# 4_PT100.net
KiCad netlist of a schematic drawn in Altium Designer
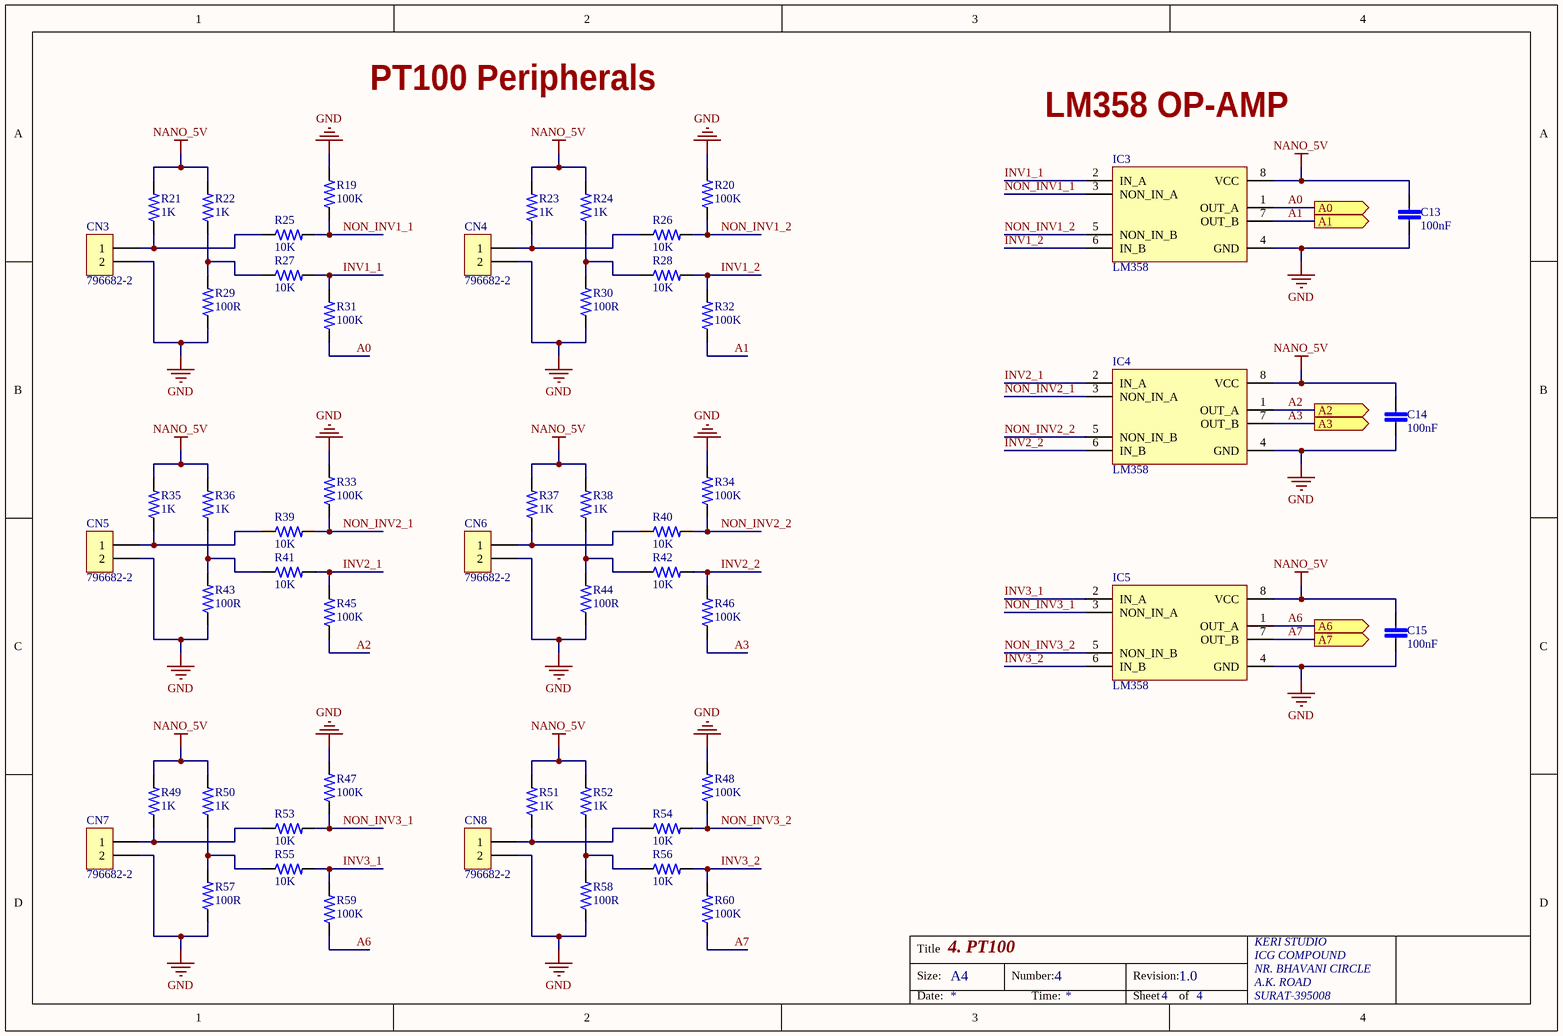
[diagram p0: 4. PT100.SchDoc]

(export (version "E")
  (design (tool "Eeschema 10.0.6"))
  (components
    (comp (ref "C13")
      (value "100nF")
      (footprint "C0805")
      (description "Multilayer Ceramic Capacitors MLCC - SMD/SMT 0805 0.1uF 50volts X7R 20%")
      (fields
        (field (name "MANUFACTURER") "Murata")
        (field (name "MANUFACTURER PART NUMBER") "GCJ21BR71H104MA01L")
      )
      (libsource (lib "keri_lib") (part "C_0805_0.1uF"))
    )
    (comp (ref "C14")
      (value "100nF")
      (footprint "C0805")
      (description "Multilayer Ceramic Capacitors MLCC - SMD/SMT 0805 0.1uF 50volts X7R 20%")
      (fields
        (field (name "MANUFACTURER") "Murata")
        (field (name "MANUFACTURER PART NUMBER") "GCJ21BR71H104MA01L")
      )
      (libsource (lib "keri_lib") (part "C_0805_0.1uF"))
    )
    (comp (ref "C15")
      (value "100nF")
      (footprint "C0805")
      (description "Multilayer Ceramic Capacitors MLCC - SMD/SMT 0805 0.1uF 50volts X7R 20%")
      (fields
        (field (name "MANUFACTURER") "Murata")
        (field (name "MANUFACTURER PART NUMBER") "GCJ21BR71H104MA01L")
      )
      (libsource (lib "keri_lib") (part "C_0805_0.1uF"))
    )
    (comp (ref "CN3")
      (value "796682-2")
      (footprint "Terminal_5.08mm_1X02")
      (description "Fixed Terminal Blocks TERMI-BLOK PCB")
      (fields (field (name "MANUFACTURER") "TE Connectivity") (field (name "VOLTAGE") "300V"))
      (libsource (lib "keri_lib") (part "Terminal_5.08mm_1X02"))
    )
    (comp (ref "CN4")
      (value "796682-2")
      (footprint "Terminal_5.08mm_1X02")
      (description "Fixed Terminal Blocks TERMI-BLOK PCB")
      (fields (field (name "MANUFACTURER") "TE Connectivity") (field (name "VOLTAGE") "300V"))
      (libsource (lib "keri_lib") (part "Terminal_5.08mm_1X02"))
    )
    (comp (ref "CN5")
      (value "796682-2")
      (footprint "Terminal_5.08mm_1X02")
      (description "Fixed Terminal Blocks TERMI-BLOK PCB")
      (fields (field (name "MANUFACTURER") "TE Connectivity") (field (name "VOLTAGE") "300V"))
      (libsource (lib "keri_lib") (part "Terminal_5.08mm_1X02"))
    )
    (comp (ref "CN6")
      (value "796682-2")
      (footprint "Terminal_5.08mm_1X02")
      (description "Fixed Terminal Blocks TERMI-BLOK PCB")
      (fields (field (name "MANUFACTURER") "TE Connectivity") (field (name "VOLTAGE") "300V"))
      (libsource (lib "keri_lib") (part "Terminal_5.08mm_1X02"))
    )
    (comp (ref "CN7")
      (value "796682-2")
      (footprint "Terminal_5.08mm_1X02")
      (description "Fixed Terminal Blocks TERMI-BLOK PCB")
      (fields (field (name "MANUFACTURER") "TE Connectivity") (field (name "VOLTAGE") "300V"))
      (libsource (lib "keri_lib") (part "Terminal_5.08mm_1X02"))
    )
    (comp (ref "CN8")
      (value "796682-2")
      (footprint "Terminal_5.08mm_1X02")
      (description "Fixed Terminal Blocks TERMI-BLOK PCB")
      (fields (field (name "MANUFACTURER") "TE Connectivity") (field (name "VOLTAGE") "300V"))
      (libsource (lib "keri_lib") (part "Terminal_5.08mm_1X02"))
    )
    (comp (ref "IC3")
      (value "LM358")
      (footprint "DIP-08")
      (description "IC OPAMP GP 700KHZ 8SOIC")
      (fields
        (field (name "MANUFACTURER") "Texas Instruments")
        (field (name "MANUFACTURER PART NUMBER") "LM358ADR")
      )
      (libsource (lib "keri_lib") (part "LM358"))
    )
    (comp (ref "IC4")
      (value "LM358")
      (footprint "DIP-08")
      (description "IC OPAMP GP 700KHZ 8SOIC")
      (fields
        (field (name "MANUFACTURER") "Texas Instruments")
        (field (name "MANUFACTURER PART NUMBER") "LM358ADR")
      )
      (libsource (lib "keri_lib") (part "LM358"))
    )
    (comp (ref "IC5")
      (value "LM358")
      (footprint "DIP-08")
      (description "IC OPAMP GP 700KHZ 8SOIC")
      (fields
        (field (name "MANUFACTURER") "Texas Instruments")
        (field (name "MANUFACTURER PART NUMBER") "LM358ADR")
      )
      (libsource (lib "keri_lib") (part "LM358"))
    )
    (comp (ref "R19")
      (value "100K")
      (footprint "R0805")
      (description "Thick Film Resistors - SMD 100K 0805 5%")
      (fields (field (name "MANUFACTURER") "Bourns") (field (name "TOLERANCE") "5%"))
      (libsource (lib "keri_lib") (part "R_0805_100K"))
    )
    (comp (ref "R20")
      (value "100K")
      (footprint "R0805")
      (description "Thick Film Resistors - SMD 100K 0805 5%")
      (fields (field (name "MANUFACTURER") "Bourns") (field (name "TOLERANCE") "5%"))
      (libsource (lib "keri_lib") (part "R_0805_100K"))
    )
    (comp (ref "R21")
      (value "1K")
      (footprint "R0805")
      (description "Thick Film Resistors - SMD 1K 5%")
      (fields
        (field (name "MANUFACTURER") "Bourns")
        (field (name "MANUFACTURER PART NUMBER") "CR0805-JW-102ELF")
      )
      (libsource (lib "keri_lib") (part "R_0805_1K"))
    )
    (comp (ref "R22")
      (value "1K")
      (footprint "R0805")
      (description "Thick Film Resistors - SMD 1K 5%")
      (fields
        (field (name "MANUFACTURER") "Bourns")
        (field (name "MANUFACTURER PART NUMBER") "CR0805-JW-102ELF")
      )
      (libsource (lib "keri_lib") (part "R_0805_1K"))
    )
    (comp (ref "R23")
      (value "1K")
      (footprint "R0805")
      (description "Thick Film Resistors - SMD 1K 5%")
      (fields
        (field (name "MANUFACTURER") "Bourns")
        (field (name "MANUFACTURER PART NUMBER") "CR0805-JW-102ELF")
      )
      (libsource (lib "keri_lib") (part "R_0805_1K"))
    )
    (comp (ref "R24")
      (value "1K")
      (footprint "R0805")
      (description "Thick Film Resistors - SMD 1K 5%")
      (fields
        (field (name "MANUFACTURER") "Bourns")
        (field (name "MANUFACTURER PART NUMBER") "CR0805-JW-102ELF")
      )
      (libsource (lib "keri_lib") (part "R_0805_1K"))
    )
    (comp (ref "R25")
      (value "10K")
      (footprint "R0805")
      (description "Thick Film Resistors - SMD 10K 0805 5%")
      (fields (field (name "MANUFACTURER") "Bourns") (field (name "TOLERANCE") "5%"))
      (libsource (lib "keri_lib") (part "R_0805_10K"))
    )
    (comp (ref "R26")
      (value "10K")
      (footprint "R0805")
      (description "Thick Film Resistors - SMD 10K 0805 5%")
      (fields (field (name "MANUFACTURER") "Bourns") (field (name "TOLERANCE") "5%"))
      (libsource (lib "keri_lib") (part "R_0805_10K"))
    )
    (comp (ref "R27")
      (value "10K")
      (footprint "R0805")
      (description "Thick Film Resistors - SMD 10K 0805 5%")
      (fields (field (name "MANUFACTURER") "Bourns") (field (name "TOLERANCE") "5%"))
      (libsource (lib "keri_lib") (part "R_0805_10K"))
    )
    (comp (ref "R28")
      (value "10K")
      (footprint "R0805")
      (description "Thick Film Resistors - SMD 10K 0805 5%")
      (fields (field (name "MANUFACTURER") "Bourns") (field (name "TOLERANCE") "5%"))
      (libsource (lib "keri_lib") (part "R_0805_10K"))
    )
    (comp (ref "R29")
      (value "100R")
      (footprint "R0805")
      (description "Thick Film Resistors - SMD 10ohm 5%")
      (fields
        (field (name "MANUFACTURER") "Bourns")
        (field (name "MANUFACTURER PART NUMBER") "CR0805-JW-100ELF")
      )
      (libsource (lib "keri_lib") (part "R_0805_100R"))
    )
    (comp (ref "R30")
      (value "100R")
      (footprint "R0805")
      (description "Thick Film Resistors - SMD 10ohm 5%")
      (fields
        (field (name "MANUFACTURER") "Bourns")
        (field (name "MANUFACTURER PART NUMBER") "CR0805-JW-100ELF")
      )
      (libsource (lib "keri_lib") (part "R_0805_100R"))
    )
    (comp (ref "R31")
      (value "100K")
      (footprint "R0805")
      (description "Thick Film Resistors - SMD 100K 0805 5%")
      (fields (field (name "MANUFACTURER") "Bourns") (field (name "TOLERANCE") "5%"))
      (libsource (lib "keri_lib") (part "R_0805_100K"))
    )
    (comp (ref "R32")
      (value "100K")
      (footprint "R0805")
      (description "Thick Film Resistors - SMD 100K 0805 5%")
      (fields (field (name "MANUFACTURER") "Bourns") (field (name "TOLERANCE") "5%"))
      (libsource (lib "keri_lib") (part "R_0805_100K"))
    )
    (comp (ref "R33")
      (value "100K")
      (footprint "R0805")
      (description "Thick Film Resistors - SMD 100K 0805 5%")
      (fields (field (name "MANUFACTURER") "Bourns") (field (name "TOLERANCE") "5%"))
      (libsource (lib "keri_lib") (part "R_0805_100K"))
    )
    (comp (ref "R34")
      (value "100K")
      (footprint "R0805")
      (description "Thick Film Resistors - SMD 100K 0805 5%")
      (fields (field (name "MANUFACTURER") "Bourns") (field (name "TOLERANCE") "5%"))
      (libsource (lib "keri_lib") (part "R_0805_100K"))
    )
    (comp (ref "R35")
      (value "1K")
      (footprint "R0805")
      (description "Thick Film Resistors - SMD 1K 5%")
      (fields
        (field (name "MANUFACTURER") "Bourns")
        (field (name "MANUFACTURER PART NUMBER") "CR0805-JW-102ELF")
      )
      (libsource (lib "keri_lib") (part "R_0805_1K"))
    )
    (comp (ref "R36")
      (value "1K")
      (footprint "R0805")
      (description "Thick Film Resistors - SMD 1K 5%")
      (fields
        (field (name "MANUFACTURER") "Bourns")
        (field (name "MANUFACTURER PART NUMBER") "CR0805-JW-102ELF")
      )
      (libsource (lib "keri_lib") (part "R_0805_1K"))
    )
    (comp (ref "R37")
      (value "1K")
      (footprint "R0805")
      (description "Thick Film Resistors - SMD 1K 5%")
      (fields
        (field (name "MANUFACTURER") "Bourns")
        (field (name "MANUFACTURER PART NUMBER") "CR0805-JW-102ELF")
      )
      (libsource (lib "keri_lib") (part "R_0805_1K"))
    )
    (comp (ref "R38")
      (value "1K")
      (footprint "R0805")
      (description "Thick Film Resistors - SMD 1K 5%")
      (fields
        (field (name "MANUFACTURER") "Bourns")
        (field (name "MANUFACTURER PART NUMBER") "CR0805-JW-102ELF")
      )
      (libsource (lib "keri_lib") (part "R_0805_1K"))
    )
    (comp (ref "R39")
      (value "10K")
      (footprint "R0805")
      (description "Thick Film Resistors - SMD 10K 0805 5%")
      (fields (field (name "MANUFACTURER") "Bourns") (field (name "TOLERANCE") "5%"))
      (libsource (lib "keri_lib") (part "R_0805_10K"))
    )
    (comp (ref "R40")
      (value "10K")
      (footprint "R0805")
      (description "Thick Film Resistors - SMD 10K 0805 5%")
      (fields (field (name "MANUFACTURER") "Bourns") (field (name "TOLERANCE") "5%"))
      (libsource (lib "keri_lib") (part "R_0805_10K"))
    )
    (comp (ref "R41")
      (value "10K")
      (footprint "R0805")
      (description "Thick Film Resistors - SMD 10K 0805 5%")
      (fields (field (name "MANUFACTURER") "Bourns") (field (name "TOLERANCE") "5%"))
      (libsource (lib "keri_lib") (part "R_0805_10K"))
    )
    (comp (ref "R42")
      (value "10K")
      (footprint "R0805")
      (description "Thick Film Resistors - SMD 10K 0805 5%")
      (fields (field (name "MANUFACTURER") "Bourns") (field (name "TOLERANCE") "5%"))
      (libsource (lib "keri_lib") (part "R_0805_10K"))
    )
    (comp (ref "R43")
      (value "100R")
      (footprint "R0805")
      (description "Thick Film Resistors - SMD 10ohm 5%")
      (fields
        (field (name "MANUFACTURER") "Bourns")
        (field (name "MANUFACTURER PART NUMBER") "CR0805-JW-100ELF")
      )
      (libsource (lib "keri_lib") (part "R_0805_100R"))
    )
    (comp (ref "R44")
      (value "100R")
      (footprint "R0805")
      (description "Thick Film Resistors - SMD 10ohm 5%")
      (fields
        (field (name "MANUFACTURER") "Bourns")
        (field (name "MANUFACTURER PART NUMBER") "CR0805-JW-100ELF")
      )
      (libsource (lib "keri_lib") (part "R_0805_100R"))
    )
    (comp (ref "R45")
      (value "100K")
      (footprint "R0805")
      (description "Thick Film Resistors - SMD 100K 0805 5%")
      (fields (field (name "MANUFACTURER") "Bourns") (field (name "TOLERANCE") "5%"))
      (libsource (lib "keri_lib") (part "R_0805_100K"))
    )
    (comp (ref "R46")
      (value "100K")
      (footprint "R0805")
      (description "Thick Film Resistors - SMD 100K 0805 5%")
      (fields (field (name "MANUFACTURER") "Bourns") (field (name "TOLERANCE") "5%"))
      (libsource (lib "keri_lib") (part "R_0805_100K"))
    )
    (comp (ref "R47")
      (value "100K")
      (footprint "R0805")
      (description "Thick Film Resistors - SMD 100K 0805 5%")
      (fields (field (name "MANUFACTURER") "Bourns") (field (name "TOLERANCE") "5%"))
      (libsource (lib "keri_lib") (part "R_0805_100K"))
    )
    (comp (ref "R48")
      (value "100K")
      (footprint "R0805")
      (description "Thick Film Resistors - SMD 100K 0805 5%")
      (fields (field (name "MANUFACTURER") "Bourns") (field (name "TOLERANCE") "5%"))
      (libsource (lib "keri_lib") (part "R_0805_100K"))
    )
    (comp (ref "R49")
      (value "1K")
      (footprint "R0805")
      (description "Thick Film Resistors - SMD 1K 5%")
      (fields
        (field (name "MANUFACTURER") "Bourns")
        (field (name "MANUFACTURER PART NUMBER") "CR0805-JW-102ELF")
      )
      (libsource (lib "keri_lib") (part "R_0805_1K"))
    )
    (comp (ref "R50")
      (value "1K")
      (footprint "R0805")
      (description "Thick Film Resistors - SMD 1K 5%")
      (fields
        (field (name "MANUFACTURER") "Bourns")
        (field (name "MANUFACTURER PART NUMBER") "CR0805-JW-102ELF")
      )
      (libsource (lib "keri_lib") (part "R_0805_1K"))
    )
    (comp (ref "R51")
      (value "1K")
      (footprint "R0805")
      (description "Thick Film Resistors - SMD 1K 5%")
      (fields
        (field (name "MANUFACTURER") "Bourns")
        (field (name "MANUFACTURER PART NUMBER") "CR0805-JW-102ELF")
      )
      (libsource (lib "keri_lib") (part "R_0805_1K"))
    )
    (comp (ref "R52")
      (value "1K")
      (footprint "R0805")
      (description "Thick Film Resistors - SMD 1K 5%")
      (fields
        (field (name "MANUFACTURER") "Bourns")
        (field (name "MANUFACTURER PART NUMBER") "CR0805-JW-102ELF")
      )
      (libsource (lib "keri_lib") (part "R_0805_1K"))
    )
    (comp (ref "R53")
      (value "10K")
      (footprint "R0805")
      (description "Thick Film Resistors - SMD 10K 0805 5%")
      (fields (field (name "MANUFACTURER") "Bourns") (field (name "TOLERANCE") "5%"))
      (libsource (lib "keri_lib") (part "R_0805_10K"))
    )
    (comp (ref "R54")
      (value "10K")
      (footprint "R0805")
      (description "Thick Film Resistors - SMD 10K 0805 5%")
      (fields (field (name "MANUFACTURER") "Bourns") (field (name "TOLERANCE") "5%"))
      (libsource (lib "keri_lib") (part "R_0805_10K"))
    )
    (comp (ref "R55")
      (value "10K")
      (footprint "R0805")
      (description "Thick Film Resistors - SMD 10K 0805 5%")
      (fields (field (name "MANUFACTURER") "Bourns") (field (name "TOLERANCE") "5%"))
      (libsource (lib "keri_lib") (part "R_0805_10K"))
    )
    (comp (ref "R56")
      (value "10K")
      (footprint "R0805")
      (description "Thick Film Resistors - SMD 10K 0805 5%")
      (fields (field (name "MANUFACTURER") "Bourns") (field (name "TOLERANCE") "5%"))
      (libsource (lib "keri_lib") (part "R_0805_10K"))
    )
    (comp (ref "R57")
      (value "100R")
      (footprint "R0805")
      (description "Thick Film Resistors - SMD 10ohm 5%")
      (fields
        (field (name "MANUFACTURER") "Bourns")
        (field (name "MANUFACTURER PART NUMBER") "CR0805-JW-100ELF")
      )
      (libsource (lib "keri_lib") (part "R_0805_100R"))
    )
    (comp (ref "R58")
      (value "100R")
      (footprint "R0805")
      (description "Thick Film Resistors - SMD 10ohm 5%")
      (fields
        (field (name "MANUFACTURER") "Bourns")
        (field (name "MANUFACTURER PART NUMBER") "CR0805-JW-100ELF")
      )
      (libsource (lib "keri_lib") (part "R_0805_100R"))
    )
    (comp (ref "R59")
      (value "100K")
      (footprint "R0805")
      (description "Thick Film Resistors - SMD 100K 0805 5%")
      (fields (field (name "MANUFACTURER") "Bourns") (field (name "TOLERANCE") "5%"))
      (libsource (lib "keri_lib") (part "R_0805_100K"))
    )
    (comp (ref "R60")
      (value "100K")
      (footprint "R0805")
      (description "Thick Film Resistors - SMD 100K 0805 5%")
      (fields (field (name "MANUFACTURER") "Bourns") (field (name "TOLERANCE") "5%"))
      (libsource (lib "keri_lib") (part "R_0805_100K"))
    )
  )
  (nets
    (net (code "1") (name "/A0") (class "Default")
      (node (ref "IC3") (pin "1") (pinfunction "OUT_A_1") (pintype "passive"))
      (node (ref "R31") (pin "1") (pinfunction "1_1") (pintype "passive"))
    )
    (net (code "2") (name "/A1") (class "Default")
      (node (ref "IC3") (pin "7") (pinfunction "OUT_B_7") (pintype "passive"))
      (node (ref "R32") (pin "1") (pinfunction "1_1") (pintype "passive"))
    )
    (net (code "3") (name "/A2") (class "Default")
      (node (ref "IC4") (pin "1") (pinfunction "OUT_A_1") (pintype "passive"))
      (node (ref "R45") (pin "1") (pinfunction "1_1") (pintype "passive"))
    )
    (net (code "4") (name "/A3") (class "Default")
      (node (ref "IC4") (pin "7") (pinfunction "OUT_B_7") (pintype "passive"))
      (node (ref "R46") (pin "1") (pinfunction "1_1") (pintype "passive"))
    )
    (net (code "5") (name "/A6") (class "Default")
      (node (ref "IC5") (pin "1") (pinfunction "OUT_A_1") (pintype "passive"))
      (node (ref "R59") (pin "1") (pinfunction "1_1") (pintype "passive"))
    )
    (net (code "6") (name "/A7") (class "Default")
      (node (ref "IC5") (pin "7") (pinfunction "OUT_B_7") (pintype "passive"))
      (node (ref "R60") (pin "1") (pinfunction "1_1") (pintype "passive"))
    )
    (net (code "7") (name "/INV1_1") (class "Default")
      (node (ref "IC3") (pin "2") (pinfunction "IN_A_2") (pintype "passive"))
      (node (ref "R27") (pin "2") (pinfunction "2_2") (pintype "passive"))
      (node (ref "R31") (pin "2") (pinfunction "2_2") (pintype "passive"))
    )
    (net (code "8") (name "/INV1_2") (class "Default")
      (node (ref "IC3") (pin "6") (pinfunction "IN_B_6") (pintype "passive"))
      (node (ref "R28") (pin "2") (pinfunction "2_2") (pintype "passive"))
      (node (ref "R32") (pin "2") (pinfunction "2_2") (pintype "passive"))
    )
    (net (code "9") (name "/INV2_1") (class "Default")
      (node (ref "IC4") (pin "2") (pinfunction "IN_A_2") (pintype "passive"))
      (node (ref "R41") (pin "2") (pinfunction "2_2") (pintype "passive"))
      (node (ref "R45") (pin "2") (pinfunction "2_2") (pintype "passive"))
    )
    (net (code "10") (name "/INV2_2") (class "Default")
      (node (ref "IC4") (pin "6") (pinfunction "IN_B_6") (pintype "passive"))
      (node (ref "R42") (pin "2") (pinfunction "2_2") (pintype "passive"))
      (node (ref "R46") (pin "2") (pinfunction "2_2") (pintype "passive"))
    )
    (net (code "11") (name "/INV3_1") (class "Default")
      (node (ref "IC5") (pin "2") (pinfunction "IN_A_2") (pintype "passive"))
      (node (ref "R55") (pin "2") (pinfunction "2_2") (pintype "passive"))
      (node (ref "R59") (pin "2") (pinfunction "2_2") (pintype "passive"))
    )
    (net (code "12") (name "/INV3_2") (class "Default")
      (node (ref "IC5") (pin "6") (pinfunction "IN_B_6") (pintype "passive"))
      (node (ref "R56") (pin "2") (pinfunction "2_2") (pintype "passive"))
      (node (ref "R60") (pin "2") (pinfunction "2_2") (pintype "passive"))
    )
    (net (code "13") (name "/NON_INV1_1") (class "Default")
      (node (ref "IC3") (pin "3") (pinfunction "NON_IN_A_3") (pintype "passive"))
      (node (ref "R19") (pin "1") (pinfunction "1_1") (pintype "passive"))
      (node (ref "R25") (pin "2") (pinfunction "2_2") (pintype "passive"))
    )
    (net (code "14") (name "/NON_INV1_2") (class "Default")
      (node (ref "IC3") (pin "5") (pinfunction "NON_IN_B_5") (pintype "passive"))
      (node (ref "R20") (pin "1") (pinfunction "1_1") (pintype "passive"))
      (node (ref "R26") (pin "2") (pinfunction "2_2") (pintype "passive"))
    )
    (net (code "15") (name "/NON_INV2_1") (class "Default")
      (node (ref "IC4") (pin "3") (pinfunction "NON_IN_A_3") (pintype "passive"))
      (node (ref "R33") (pin "1") (pinfunction "1_1") (pintype "passive"))
      (node (ref "R39") (pin "2") (pinfunction "2_2") (pintype "passive"))
    )
    (net (code "16") (name "/NON_INV2_2") (class "Default")
      (node (ref "IC4") (pin "5") (pinfunction "NON_IN_B_5") (pintype "passive"))
      (node (ref "R34") (pin "1") (pinfunction "1_1") (pintype "passive"))
      (node (ref "R40") (pin "2") (pinfunction "2_2") (pintype "passive"))
    )
    (net (code "17") (name "/NON_INV3_1") (class "Default")
      (node (ref "IC5") (pin "3") (pinfunction "NON_IN_A_3") (pintype "passive"))
      (node (ref "R47") (pin "1") (pinfunction "1_1") (pintype "passive"))
      (node (ref "R53") (pin "2") (pinfunction "2_2") (pintype "passive"))
    )
    (net (code "18") (name "/NON_INV3_2") (class "Default")
      (node (ref "IC5") (pin "5") (pinfunction "NON_IN_B_5") (pintype "passive"))
      (node (ref "R48") (pin "1") (pinfunction "1_1") (pintype "passive"))
      (node (ref "R54") (pin "2") (pinfunction "2_2") (pintype "passive"))
    )
    (net (code "19") (name "GND") (class "Default")
      (node (ref "C13") (pin "2") (pinfunction "2_2") (pintype "passive"))
      (node (ref "C14") (pin "2") (pinfunction "2_2") (pintype "passive"))
      (node (ref "C15") (pin "2") (pinfunction "2_2") (pintype "passive"))
      (node (ref "CN3") (pin "2") (pinfunction "2_2") (pintype "passive"))
      (node (ref "CN4") (pin "2") (pinfunction "2_2") (pintype "passive"))
      (node (ref "CN5") (pin "2") (pinfunction "2_2") (pintype "passive"))
      (node (ref "CN6") (pin "2") (pinfunction "2_2") (pintype "passive"))
      (node (ref "CN7") (pin "2") (pinfunction "2_2") (pintype "passive"))
      (node (ref "CN8") (pin "2") (pinfunction "2_2") (pintype "passive"))
      (node (ref "IC3") (pin "4") (pinfunction "GND_4") (pintype "passive"))
      (node (ref "IC4") (pin "4") (pinfunction "GND_4") (pintype "passive"))
      (node (ref "IC5") (pin "4") (pinfunction "GND_4") (pintype "passive"))
      (node (ref "R19") (pin "2") (pinfunction "2_2") (pintype "passive"))
      (node (ref "R20") (pin "2") (pinfunction "2_2") (pintype "passive"))
      (node (ref "R29") (pin "1") (pinfunction "1_1") (pintype "passive"))
      (node (ref "R30") (pin "1") (pinfunction "1_1") (pintype "passive"))
      (node (ref "R33") (pin "2") (pinfunction "2_2") (pintype "passive"))
      (node (ref "R34") (pin "2") (pinfunction "2_2") (pintype "passive"))
      (node (ref "R43") (pin "1") (pinfunction "1_1") (pintype "passive"))
      (node (ref "R44") (pin "1") (pinfunction "1_1") (pintype "passive"))
      (node (ref "R47") (pin "2") (pinfunction "2_2") (pintype "passive"))
      (node (ref "R48") (pin "2") (pinfunction "2_2") (pintype "passive"))
      (node (ref "R57") (pin "1") (pinfunction "1_1") (pintype "passive"))
      (node (ref "R58") (pin "1") (pinfunction "1_1") (pintype "passive"))
    )
    (net (code "20") (name "NANO_5V") (class "Default")
      (node (ref "C13") (pin "1") (pinfunction "1_1") (pintype "passive"))
      (node (ref "C14") (pin "1") (pinfunction "1_1") (pintype "passive"))
      (node (ref "C15") (pin "1") (pinfunction "1_1") (pintype "passive"))
      (node (ref "IC3") (pin "8") (pinfunction "VCC_8") (pintype "passive"))
      (node (ref "IC4") (pin "8") (pinfunction "VCC_8") (pintype "passive"))
      (node (ref "IC5") (pin "8") (pinfunction "VCC_8") (pintype "passive"))
      (node (ref "R21") (pin "2") (pinfunction "2_2") (pintype "passive"))
      (node (ref "R22") (pin "2") (pinfunction "2_2") (pintype "passive"))
      (node (ref "R23") (pin "2") (pinfunction "2_2") (pintype "passive"))
      (node (ref "R24") (pin "2") (pinfunction "2_2") (pintype "passive"))
      (node (ref "R35") (pin "2") (pinfunction "2_2") (pintype "passive"))
      (node (ref "R36") (pin "2") (pinfunction "2_2") (pintype "passive"))
      (node (ref "R37") (pin "2") (pinfunction "2_2") (pintype "passive"))
      (node (ref "R38") (pin "2") (pinfunction "2_2") (pintype "passive"))
      (node (ref "R49") (pin "2") (pinfunction "2_2") (pintype "passive"))
      (node (ref "R50") (pin "2") (pinfunction "2_2") (pintype "passive"))
      (node (ref "R51") (pin "2") (pinfunction "2_2") (pintype "passive"))
      (node (ref "R52") (pin "2") (pinfunction "2_2") (pintype "passive"))
    )
    (net (code "21") (name "Net-(CN3-Pad1)") (class "Default")
      (node (ref "CN3") (pin "1") (pinfunction "1_1") (pintype "passive"))
      (node (ref "R21") (pin "1") (pinfunction "1_1") (pintype "passive"))
      (node (ref "R25") (pin "1") (pinfunction "1_1") (pintype "passive"))
    )
    (net (code "22") (name "Net-(CN4-Pad1)") (class "Default")
      (node (ref "CN4") (pin "1") (pinfunction "1_1") (pintype "passive"))
      (node (ref "R23") (pin "1") (pinfunction "1_1") (pintype "passive"))
      (node (ref "R26") (pin "1") (pinfunction "1_1") (pintype "passive"))
    )
    (net (code "23") (name "Net-(CN5-Pad1)") (class "Default")
      (node (ref "CN5") (pin "1") (pinfunction "1_1") (pintype "passive"))
      (node (ref "R35") (pin "1") (pinfunction "1_1") (pintype "passive"))
      (node (ref "R39") (pin "1") (pinfunction "1_1") (pintype "passive"))
    )
    (net (code "24") (name "Net-(CN6-Pad1)") (class "Default")
      (node (ref "CN6") (pin "1") (pinfunction "1_1") (pintype "passive"))
      (node (ref "R37") (pin "1") (pinfunction "1_1") (pintype "passive"))
      (node (ref "R40") (pin "1") (pinfunction "1_1") (pintype "passive"))
    )
    (net (code "25") (name "Net-(CN7-Pad1)") (class "Default")
      (node (ref "CN7") (pin "1") (pinfunction "1_1") (pintype "passive"))
      (node (ref "R49") (pin "1") (pinfunction "1_1") (pintype "passive"))
      (node (ref "R53") (pin "1") (pinfunction "1_1") (pintype "passive"))
    )
    (net (code "26") (name "Net-(CN8-Pad1)") (class "Default")
      (node (ref "CN8") (pin "1") (pinfunction "1_1") (pintype "passive"))
      (node (ref "R51") (pin "1") (pinfunction "1_1") (pintype "passive"))
      (node (ref "R54") (pin "1") (pinfunction "1_1") (pintype "passive"))
    )
    (net (code "27") (name "Net-(R22-Pad1)") (class "Default")
      (node (ref "R22") (pin "1") (pinfunction "1_1") (pintype "passive"))
      (node (ref "R27") (pin "1") (pinfunction "1_1") (pintype "passive"))
      (node (ref "R29") (pin "2") (pinfunction "2_2") (pintype "passive"))
    )
    (net (code "28") (name "Net-(R24-Pad1)") (class "Default")
      (node (ref "R24") (pin "1") (pinfunction "1_1") (pintype "passive"))
      (node (ref "R28") (pin "1") (pinfunction "1_1") (pintype "passive"))
      (node (ref "R30") (pin "2") (pinfunction "2_2") (pintype "passive"))
    )
    (net (code "29") (name "Net-(R36-Pad1)") (class "Default")
      (node (ref "R36") (pin "1") (pinfunction "1_1") (pintype "passive"))
      (node (ref "R41") (pin "1") (pinfunction "1_1") (pintype "passive"))
      (node (ref "R43") (pin "2") (pinfunction "2_2") (pintype "passive"))
    )
    (net (code "30") (name "Net-(R38-Pad1)") (class "Default")
      (node (ref "R38") (pin "1") (pinfunction "1_1") (pintype "passive"))
      (node (ref "R42") (pin "1") (pinfunction "1_1") (pintype "passive"))
      (node (ref "R44") (pin "2") (pinfunction "2_2") (pintype "passive"))
    )
    (net (code "31") (name "Net-(R50-Pad1)") (class "Default")
      (node (ref "R50") (pin "1") (pinfunction "1_1") (pintype "passive"))
      (node (ref "R55") (pin "1") (pinfunction "1_1") (pintype "passive"))
      (node (ref "R57") (pin "2") (pinfunction "2_2") (pintype "passive"))
    )
    (net (code "32") (name "Net-(R52-Pad1)") (class "Default")
      (node (ref "R52") (pin "1") (pinfunction "1_1") (pintype "passive"))
      (node (ref "R56") (pin "1") (pinfunction "1_1") (pintype "passive"))
      (node (ref "R58") (pin "2") (pinfunction "2_2") (pintype "passive"))
    )
  )
)
